# Apex3.net
KiCad netlist of a schematic drawn in EAGLE
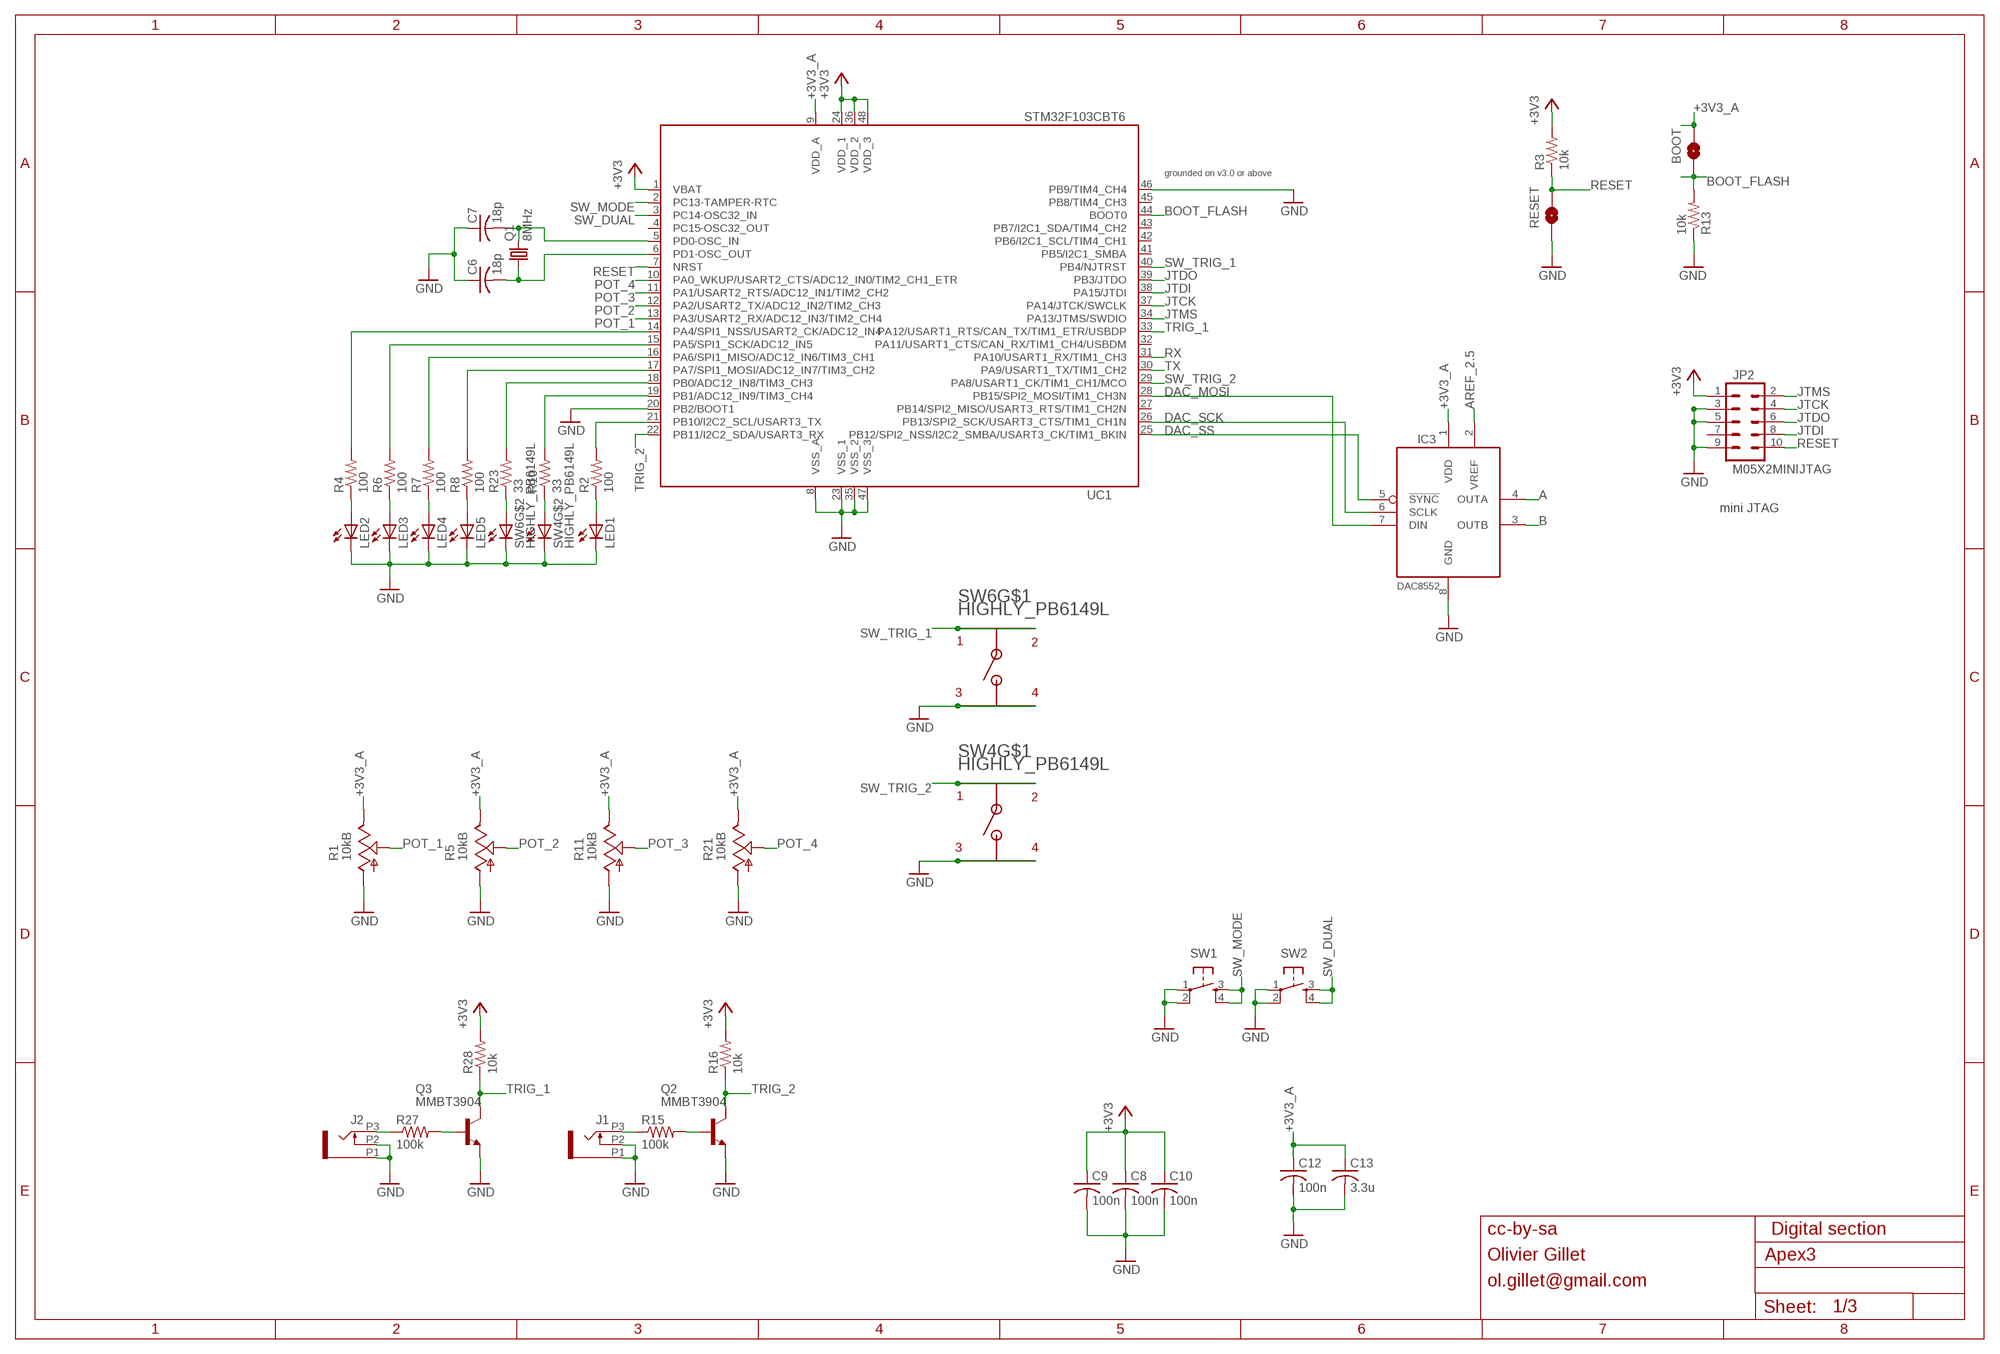
[diagram p0: schematic, sheet 1]
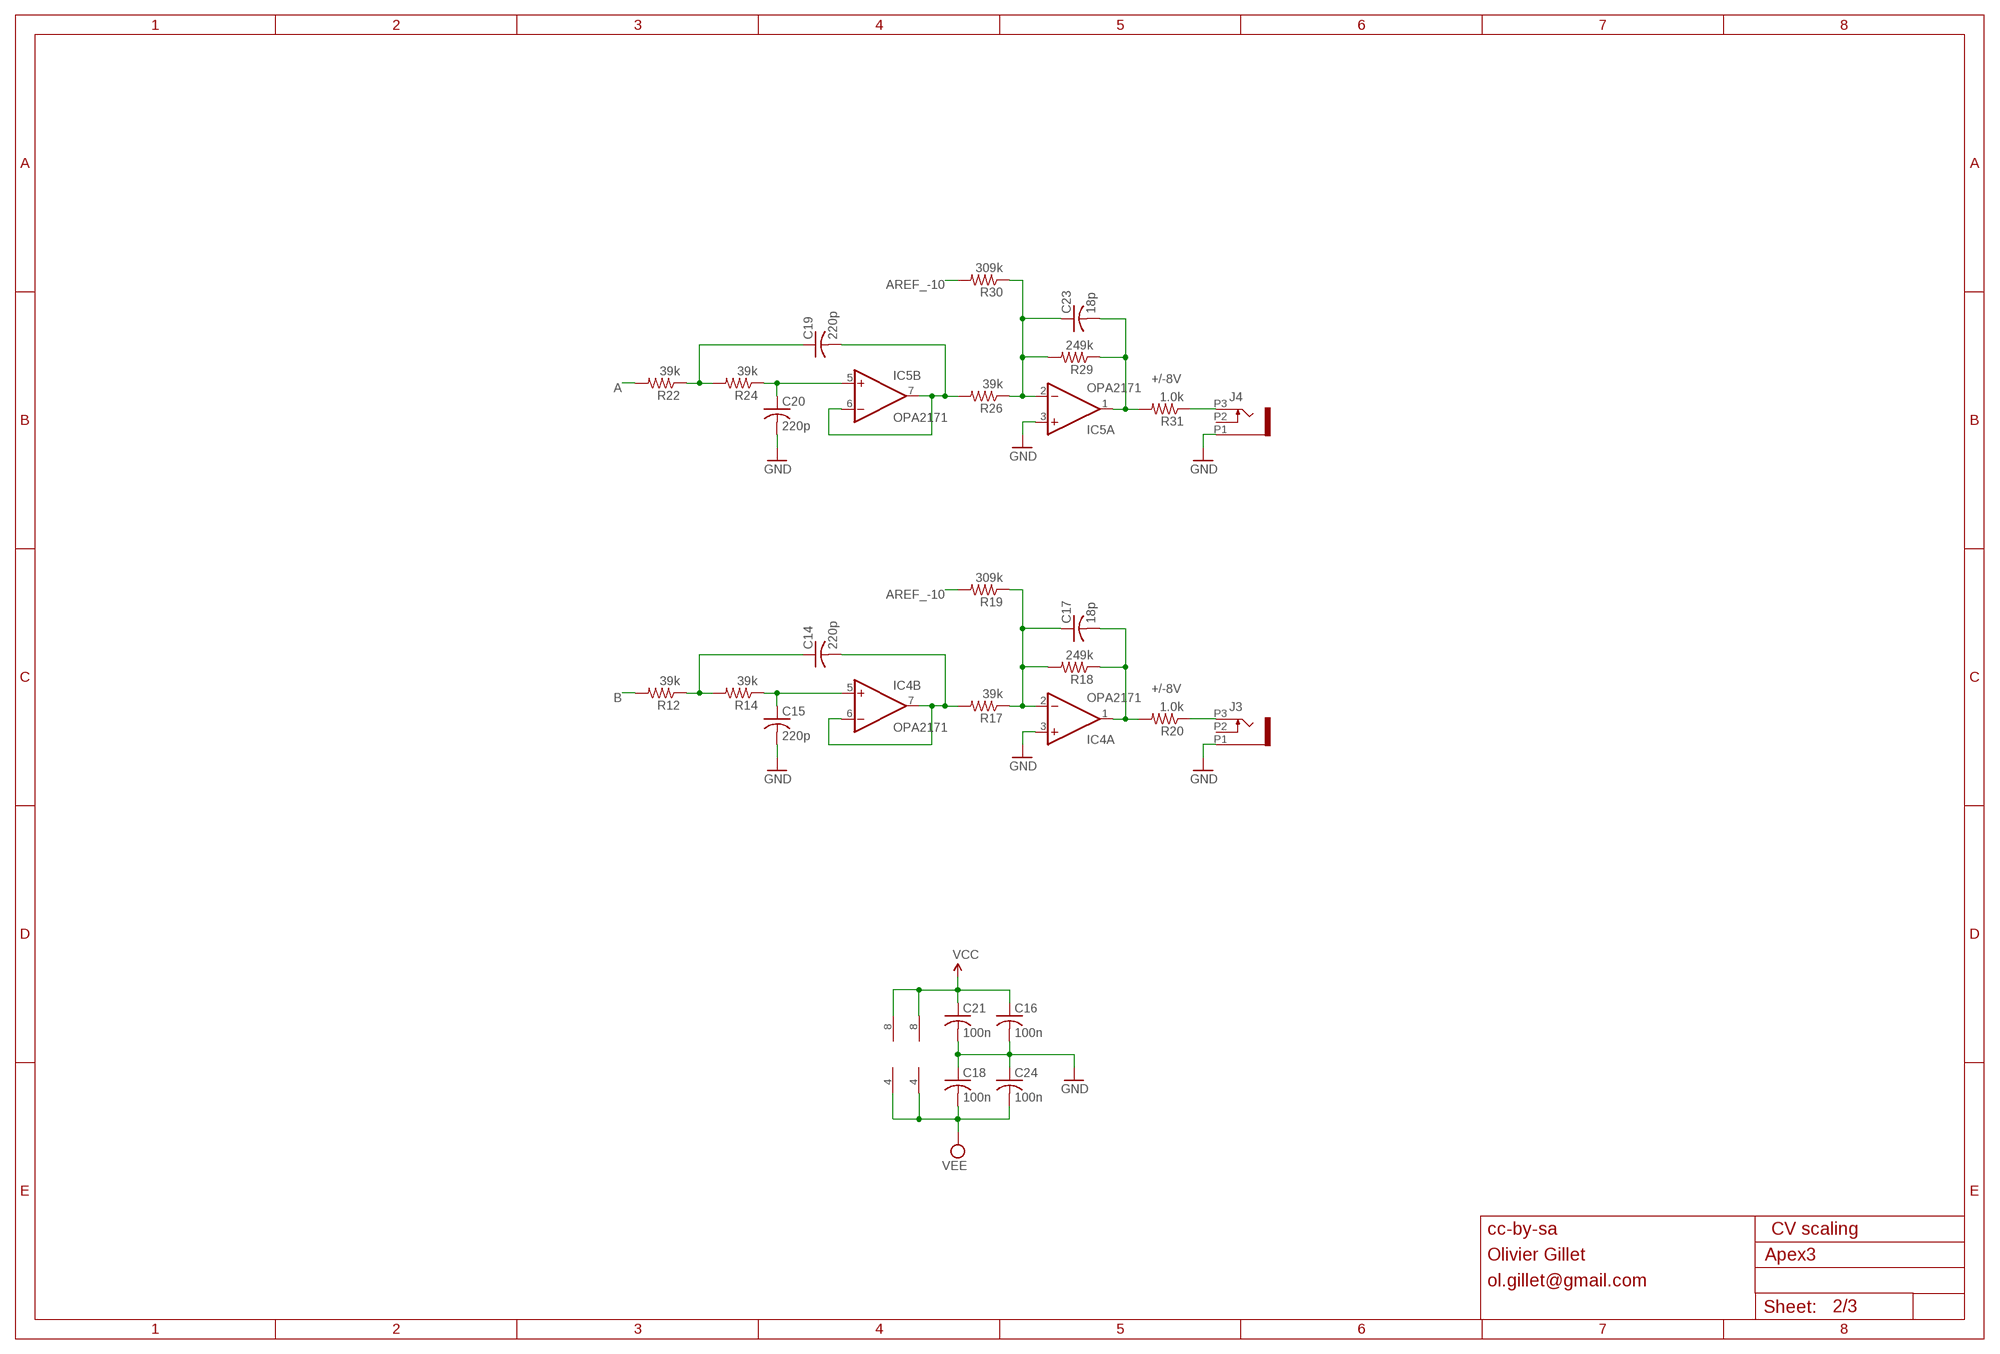
[diagram p1: schematic, sheet 2]
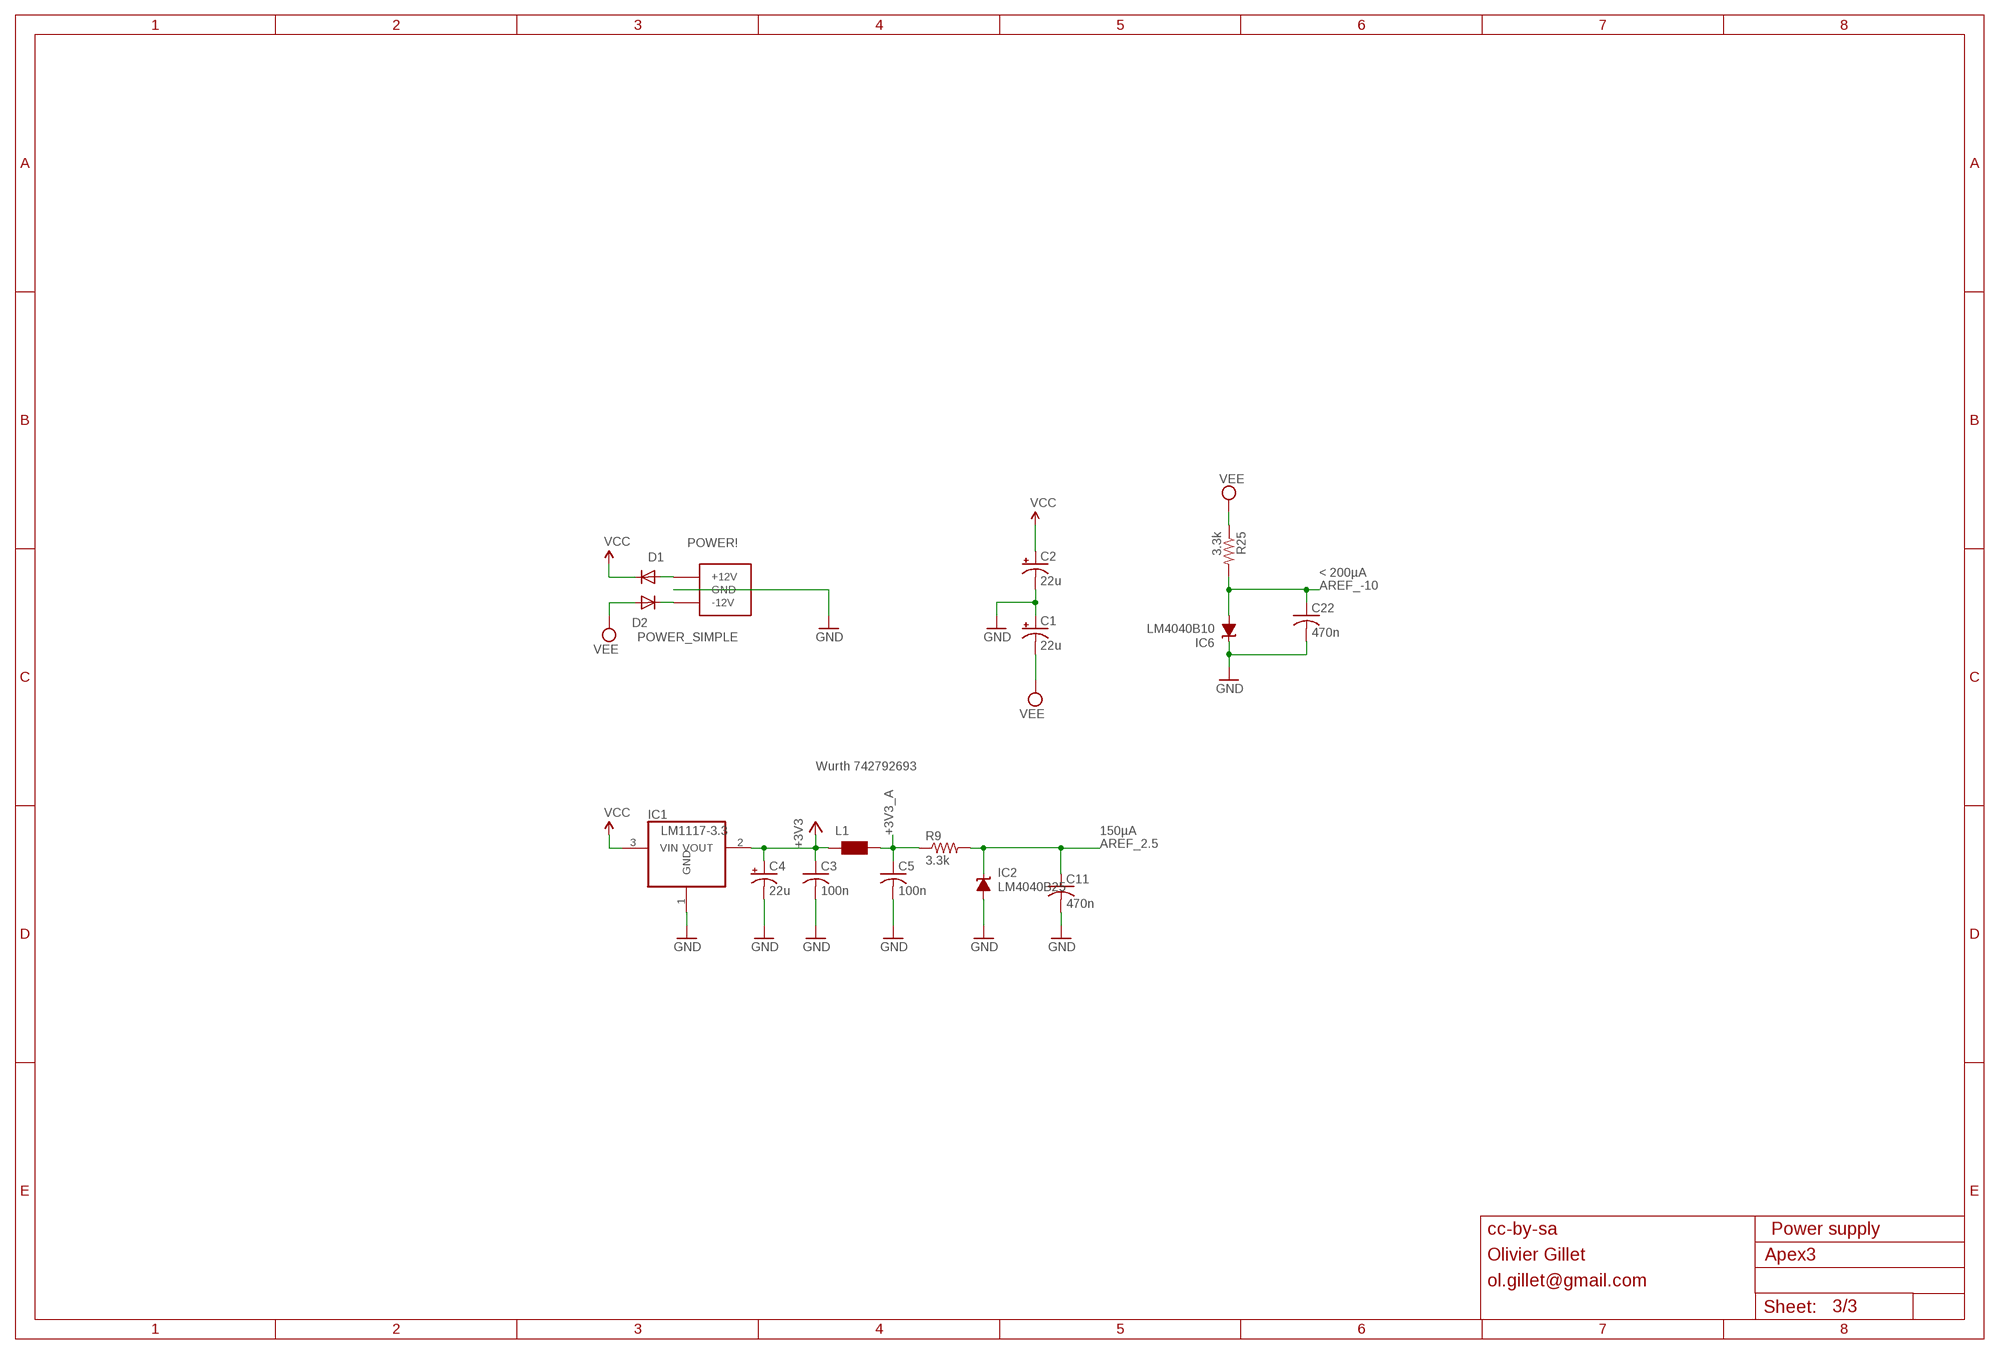
[diagram p2: schematic, sheet 3]

(export (version "E")
  (design (tool "Eeschema 10.0.6"))
  (components
    (comp (ref "C14")
      (value "220p")
      (footprint "eagle-import:C0603")
      (libsource (lib "eagle-import") (part "C-USC0603"))
    )
    (comp (ref "C15")
      (value "220p")
      (footprint "eagle-import:C0603")
      (libsource (lib "eagle-import") (part "C-USC0603"))
    )
    (comp (ref "C16")
      (value "100n")
      (footprint "eagle-import:C0603")
      (libsource (lib "eagle-import") (part "C-USC0603"))
    )
    (comp (ref "C17")
      (value "18p")
      (footprint "eagle-import:C0603")
      (libsource (lib "eagle-import") (part "C-USC0603"))
    )
    (comp (ref "C18")
      (value "100n")
      (footprint "eagle-import:C0603")
      (libsource (lib "eagle-import") (part "C-USC0603"))
    )
    (comp (ref "C19")
      (value "220p")
      (footprint "eagle-import:C0603")
      (libsource (lib "eagle-import") (part "C-USC0603"))
    )
    (comp (ref "C20")
      (value "220p")
      (footprint "eagle-import:C0603")
      (libsource (lib "eagle-import") (part "C-USC0603"))
    )
    (comp (ref "C21")
      (value "100n")
      (footprint "eagle-import:C0603")
      (libsource (lib "eagle-import") (part "C-USC0603"))
    )
    (comp (ref "C23")
      (value "18p")
      (footprint "eagle-import:C0603")
      (libsource (lib "eagle-import") (part "C-USC0603"))
    )
    (comp (ref "C24")
      (value "100n")
      (footprint "eagle-import:C0603")
      (libsource (lib "eagle-import") (part "C-USC0603"))
    )
    (comp (ref "IC4")
      (value "OPA2171")
      (footprint "eagle-import:SO08")
      (libsource (lib "eagle-import") (part "TL072D"))
    )
    (comp (ref "IC5")
      (value "OPA2171")
      (footprint "eagle-import:SO08")
      (libsource (lib "eagle-import") (part "TL072D"))
    )
    (comp (ref "J3")
      (value "OG-PJ301_PJ301_THONKICONN")
      (footprint "eagle-import:OG-PJ301_WQP_PJ_301M6_NO_HOLE")
      (libsource (lib "eagle-import") (part "OG-PJ301_PJ301_THONKICONN"))
    )
    (comp (ref "J4")
      (value "OG-PJ301_PJ301_THONKICONN")
      (footprint "eagle-import:OG-PJ301_WQP_PJ_301M6_NO_HOLE")
      (libsource (lib "eagle-import") (part "OG-PJ301_PJ301_THONKICONN"))
    )
    (comp (ref "R12")
      (value "39k")
      (footprint "eagle-import:R0603")
      (libsource (lib "eagle-import") (part "R-US_R0603"))
    )
    (comp (ref "R14")
      (value "39k")
      (footprint "eagle-import:R0603")
      (libsource (lib "eagle-import") (part "R-US_R0603"))
    )
    (comp (ref "R17")
      (value "39k")
      (footprint "eagle-import:R0603")
      (libsource (lib "eagle-import") (part "R-US_R0603"))
    )
    (comp (ref "R18")
      (value "249k")
      (footprint "eagle-import:R0603")
      (libsource (lib "eagle-import") (part "R-US_R0603"))
    )
    (comp (ref "R19")
      (value "309k")
      (footprint "eagle-import:R0603")
      (libsource (lib "eagle-import") (part "R-US_R0603"))
    )
    (comp (ref "R20")
      (value "1.0k")
      (footprint "eagle-import:R0603")
      (libsource (lib "eagle-import") (part "R-US_R0603"))
    )
    (comp (ref "R22")
      (value "39k")
      (footprint "eagle-import:R0603")
      (libsource (lib "eagle-import") (part "R-US_R0603"))
    )
    (comp (ref "R24")
      (value "39k")
      (footprint "eagle-import:R0603")
      (libsource (lib "eagle-import") (part "R-US_R0603"))
    )
    (comp (ref "R26")
      (value "39k")
      (footprint "eagle-import:R0603")
      (libsource (lib "eagle-import") (part "R-US_R0603"))
    )
    (comp (ref "R29")
      (value "249k")
      (footprint "eagle-import:R0603")
      (libsource (lib "eagle-import") (part "R-US_R0603"))
    )
    (comp (ref "R30")
      (value "309k")
      (footprint "eagle-import:R0603")
      (libsource (lib "eagle-import") (part "R-US_R0603"))
    )
    (comp (ref "R31")
      (value "1.0k")
      (footprint "eagle-import:R0603")
      (libsource (lib "eagle-import") (part "R-US_R0603"))
    )
    (comp (ref "C1")
      (value "22u")
      (footprint "eagle-import:PANASONIC_C")
      (libsource (lib "eagle-import") (part "CPOL-USC"))
    )
    (comp (ref "C2")
      (value "22u")
      (footprint "eagle-import:PANASONIC_C")
      (libsource (lib "eagle-import") (part "CPOL-USC"))
    )
    (comp (ref "C3")
      (value "100n")
      (footprint "eagle-import:C0603")
      (libsource (lib "eagle-import") (part "C-USC0603"))
    )
    (comp (ref "C4")
      (value "22u")
      (footprint "eagle-import:PANASONIC_C")
      (libsource (lib "eagle-import") (part "CPOL-USC"))
    )
    (comp (ref "C5")
      (value "100n")
      (footprint "eagle-import:C0603")
      (libsource (lib "eagle-import") (part "C-USC0603"))
    )
    (comp (ref "C11")
      (value "470n")
      (footprint "eagle-import:C0603")
      (libsource (lib "eagle-import") (part "C-USC0603"))
    )
    (comp (ref "C22")
      (value "470n")
      (footprint "eagle-import:C0603")
      (libsource (lib "eagle-import") (part "C-USC0603"))
    )
    (comp (ref "D1")
      (value "1N5819HW")
      (footprint "eagle-import:SOD123")
      (libsource (lib "eagle-import") (part "DIODE-SOD123"))
    )
    (comp (ref "D2")
      (value "1N5819HW")
      (footprint "eagle-import:SOD123")
      (libsource (lib "eagle-import") (part "DIODE-SOD123"))
    )
    (comp (ref "IC1")
      (value "LM1117-3.3")
      (footprint "eagle-import:SOT223")
      (libsource (lib "eagle-import") (part "REG1117"))
    )
    (comp (ref "IC2")
      (value "LM4040B25")
      (footprint "eagle-import:DBZ_R-PDSO-G3")
      (libsource (lib "eagle-import") (part "LM4041DBZB12"))
    )
    (comp (ref "IC6")
      (value "LM4040B10")
      (footprint "eagle-import:DBZ_R-PDSO-G3")
      (libsource (lib "eagle-import") (part "LM4041DBZB12"))
    )
    (comp (ref "L1")
      (value "WE-CBF_0603")
      (footprint "eagle-import:0603")
      (libsource (lib "eagle-import") (part "WE-CBF_0603"))
    )
    (comp (ref "POWER!")
      (value "POWER_SIMPLE")
      (footprint "eagle-import:2X05_SMT_HEADER")
      (libsource (lib "eagle-import") (part "POWER_SIMPLE"))
    )
    (comp (ref "R9")
      (value "3.3k")
      (footprint "eagle-import:R0603")
      (libsource (lib "eagle-import") (part "R-US_R0603"))
    )
    (comp (ref "R25")
      (value "3.3k")
      (footprint "eagle-import:R0603")
      (libsource (lib "eagle-import") (part "R-US_R0603"))
    )
    (comp (ref "BOOT")
      (value "BOOT")
      (footprint "eagle-import:SMT-JUMPER_2_NO_SILK")
      (libsource (lib "eagle-import") (part "JUMPER-SMT_2_NO_SILK"))
    )
    (comp (ref "C6")
      (value "18p")
      (footprint "eagle-import:C0603")
      (libsource (lib "eagle-import") (part "C-USC0603"))
    )
    (comp (ref "C7")
      (value "18p")
      (footprint "eagle-import:C0603")
      (libsource (lib "eagle-import") (part "C-USC0603"))
    )
    (comp (ref "C8")
      (value "100n")
      (footprint "eagle-import:C0603")
      (libsource (lib "eagle-import") (part "C-USC0603"))
    )
    (comp (ref "C9")
      (value "100n")
      (footprint "eagle-import:C0603")
      (libsource (lib "eagle-import") (part "C-USC0603"))
    )
    (comp (ref "C10")
      (value "100n")
      (footprint "eagle-import:C0603")
      (libsource (lib "eagle-import") (part "C-USC0603"))
    )
    (comp (ref "C12")
      (value "100n")
      (footprint "eagle-import:C0603")
      (libsource (lib "eagle-import") (part "C-USC0603"))
    )
    (comp (ref "C13")
      (value "3.3u")
      (footprint "eagle-import:C0603")
      (libsource (lib "eagle-import") (part "C-USC0603"))
    )
    (comp (ref "IC3")
      (value "DAC8552")
      (footprint "eagle-import:MSOP-8")
      (libsource (lib "eagle-import") (part "DAC8552"))
    )
    (comp (ref "J1")
      (value "OG-PJ301_PJ301_THONKICONN")
      (footprint "eagle-import:OG-PJ301_WQP_PJ_301M6_NO_HOLE")
      (libsource (lib "eagle-import") (part "OG-PJ301_PJ301_THONKICONN"))
    )
    (comp (ref "J2")
      (value "OG-PJ301_PJ301_THONKICONN")
      (footprint "eagle-import:OG-PJ301_WQP_PJ_301M6_NO_HOLE")
      (libsource (lib "eagle-import") (part "OG-PJ301_PJ301_THONKICONN"))
    )
    (comp (ref "JP2")
      (value "M05X2MINIJTAG")
      (footprint "eagle-import:2X5-1.27")
      (libsource (lib "eagle-import") (part "M05X2MINIJTAG"))
    )
    (comp (ref "LED1")
      (value "LED3MM")
      (footprint "eagle-import:LED3MM")
      (libsource (lib "eagle-import") (part "LED3MM"))
    )
    (comp (ref "LED2")
      (value "LED3MM")
      (footprint "eagle-import:LED3MM")
      (libsource (lib "eagle-import") (part "LED3MM"))
    )
    (comp (ref "LED3")
      (value "LED3MM")
      (footprint "eagle-import:LED3MM")
      (libsource (lib "eagle-import") (part "LED3MM"))
    )
    (comp (ref "LED4")
      (value "LED3MM")
      (footprint "eagle-import:LED3MM")
      (libsource (lib "eagle-import") (part "LED3MM"))
    )
    (comp (ref "LED5")
      (value "LED3MM")
      (footprint "eagle-import:LED3MM")
      (libsource (lib "eagle-import") (part "LED3MM"))
    )
    (comp (ref "Q1")
      (value "8MHz")
      (footprint "eagle-import:HC49UP")
      (libsource (lib "eagle-import") (part "CRYSTALHC49UP"))
    )
    (comp (ref "Q2")
      (value "MMBT3904")
      (footprint "eagle-import:SOT23-BEC")
      (libsource (lib "eagle-import") (part "-NPN-SOT23-BECMMBT3904LT1"))
    )
    (comp (ref "Q3")
      (value "MMBT3904")
      (footprint "eagle-import:SOT23-BEC")
      (libsource (lib "eagle-import") (part "-NPN-SOT23-BECMMBT3904LT1"))
    )
    (comp (ref "R1")
      (value "10kB")
      (footprint "eagle-import:POT-ALPS_ALPS_POT_VERTICAL")
      (libsource (lib "eagle-import") (part "POT-ALPS_POT_USVERTICAL"))
    )
    (comp (ref "R2")
      (value "100")
      (footprint "eagle-import:R0603")
      (libsource (lib "eagle-import") (part "R-US_R0603"))
    )
    (comp (ref "R3")
      (value "10k")
      (footprint "eagle-import:R0603")
      (libsource (lib "eagle-import") (part "R-US_R0603"))
    )
    (comp (ref "R4")
      (value "100")
      (footprint "eagle-import:R0603")
      (libsource (lib "eagle-import") (part "R-US_R0603"))
    )
    (comp (ref "R5")
      (value "10kB")
      (footprint "eagle-import:POT-ALPS_ALPS_POT_VERTICAL")
      (libsource (lib "eagle-import") (part "POT-ALPS_POT_USVERTICAL"))
    )
    (comp (ref "R6")
      (value "100")
      (footprint "eagle-import:R0603")
      (libsource (lib "eagle-import") (part "R-US_R0603"))
    )
    (comp (ref "R7")
      (value "100")
      (footprint "eagle-import:R0603")
      (libsource (lib "eagle-import") (part "R-US_R0603"))
    )
    (comp (ref "R8")
      (value "100")
      (footprint "eagle-import:R0603")
      (libsource (lib "eagle-import") (part "R-US_R0603"))
    )
    (comp (ref "R10")
      (value "33")
      (footprint "eagle-import:R0603")
      (libsource (lib "eagle-import") (part "R-US_R0603"))
    )
    (comp (ref "R11")
      (value "10kB")
      (footprint "eagle-import:POT-ALPS_ALPS_POT_VERTICAL")
      (libsource (lib "eagle-import") (part "POT-ALPS_POT_USVERTICAL"))
    )
    (comp (ref "R13")
      (value "10k")
      (footprint "eagle-import:R0603")
      (libsource (lib "eagle-import") (part "R-US_R0603"))
    )
    (comp (ref "R15")
      (value "100k")
      (footprint "eagle-import:R0603")
      (libsource (lib "eagle-import") (part "R-US_R0603"))
    )
    (comp (ref "R16")
      (value "10k")
      (footprint "eagle-import:R0603")
      (libsource (lib "eagle-import") (part "R-US_R0603"))
    )
    (comp (ref "R21")
      (value "10kB")
      (footprint "eagle-import:POT-ALPS_ALPS_POT_VERTICAL")
      (libsource (lib "eagle-import") (part "POT-ALPS_POT_USVERTICAL"))
    )
    (comp (ref "R23")
      (value "33")
      (footprint "eagle-import:R0603")
      (libsource (lib "eagle-import") (part "R-US_R0603"))
    )
    (comp (ref "R27")
      (value "100k")
      (footprint "eagle-import:R0603")
      (libsource (lib "eagle-import") (part "R-US_R0603"))
    )
    (comp (ref "R28")
      (value "10k")
      (footprint "eagle-import:R0603")
      (libsource (lib "eagle-import") (part "R-US_R0603"))
    )
    (comp (ref "RESET")
      (value "RESET")
      (footprint "eagle-import:SMT-JUMPER_2_NO_SILK")
      (libsource (lib "eagle-import") (part "JUMPER-SMT_2_NO_SILK"))
    )
    (comp (ref "SW1")
      (value "TAC_SWITCHPTH")
      (footprint "eagle-import:TACTILE-PTH")
      (libsource (lib "eagle-import") (part "TAC_SWITCHPTH"))
    )
    (comp (ref "SW2")
      (value "TAC_SWITCHPTH")
      (footprint "eagle-import:TACTILE-PTH")
      (libsource (lib "eagle-import") (part "TAC_SWITCHPTH"))
    )
    (comp (ref "SW4")
      (value "HIGHLY_PB6149L")
      (footprint "eagle-import:HIGHLY_PB64149L")
      (libsource (lib "eagle-import") (part "HIGHLY_PB6149L"))
    )
    (comp (ref "SW6")
      (value "HIGHLY_PB6149L")
      (footprint "eagle-import:HIGHLY_PB64149L")
      (libsource (lib "eagle-import") (part "HIGHLY_PB6149L"))
    )
    (comp (ref "UC1")
      (value "STM32F103CBT6")
      (footprint "eagle-import:LQFP48")
      (libsource (lib "eagle-import") (part "STM32F103CB"))
    )
  )
  (nets
    (net (code "1") (name "+3V3") (class "Default")
      (node (ref "C10") (pin "1") (pinfunction "1_1") (pintype "passive"))
      (node (ref "C3") (pin "1") (pinfunction "1_1") (pintype "passive"))
      (node (ref "C4") (pin "+") (pinfunction "+_+") (pintype "passive"))
      (node (ref "C8") (pin "1") (pinfunction "1_1") (pintype "passive"))
      (node (ref "C9") (pin "1") (pinfunction "1_1") (pintype "passive"))
      (node (ref "IC1") (pin "2") (pinfunction "VOUT_2") (pintype "output"))
      (node (ref "JP2") (pin "1") (pinfunction "1_1") (pintype "passive"))
      (node (ref "L1") (pin "1") (pinfunction "1_1") (pintype "passive"))
      (node (ref "R16") (pin "2") (pinfunction "2_2") (pintype "passive"))
      (node (ref "R28") (pin "2") (pinfunction "2_2") (pintype "passive"))
      (node (ref "R3") (pin "2") (pinfunction "2_2") (pintype "passive"))
      (node (ref "UC1") (pin "1") (pinfunction "VBAT_1") (pintype "power_in"))
      (node (ref "UC1") (pin "24") (pinfunction "VDD_1_24") (pintype "power_in"))
      (node (ref "UC1") (pin "36") (pinfunction "VDD_2_36") (pintype "power_in"))
      (node (ref "UC1") (pin "48") (pinfunction "VDD_3_48") (pintype "power_in"))
    )
    (net (code "2") (name "+3V3_A") (class "Default")
      (node (ref "BOOT") (pin "2") (pinfunction "2_2") (pintype "passive"))
      (node (ref "C12") (pin "1") (pinfunction "1_1") (pintype "passive"))
      (node (ref "C13") (pin "1") (pinfunction "1_1") (pintype "passive"))
      (node (ref "C5") (pin "1") (pinfunction "1_1") (pintype "passive"))
      (node (ref "IC3") (pin "1") (pinfunction "VDD_1") (pintype "power_in"))
      (node (ref "L1") (pin "2") (pinfunction "2_2") (pintype "passive"))
      (node (ref "R1") (pin "P$1") (pinfunction "E_P$1") (pintype "passive"))
      (node (ref "R11") (pin "P$1") (pinfunction "E_P$1") (pintype "passive"))
      (node (ref "R21") (pin "P$1") (pinfunction "E_P$1") (pintype "passive"))
      (node (ref "R5") (pin "P$1") (pinfunction "E_P$1") (pintype "passive"))
      (node (ref "R9") (pin "1") (pinfunction "1_1") (pintype "passive"))
      (node (ref "UC1") (pin "9") (pinfunction "VDD_A_9") (pintype "power_in"))
    )
    (net (code "3") (name "A") (class "Default")
      (node (ref "IC3") (pin "4") (pinfunction "OUTA_4") (pintype "output"))
      (node (ref "R22") (pin "2") (pinfunction "2_2") (pintype "passive"))
    )
    (net (code "4") (name "AREF_-10") (class "Default")
      (node (ref "C22") (pin "1") (pinfunction "1_1") (pintype "passive"))
      (node (ref "IC6") (pin "2") (pinfunction "A_2") (pintype "passive"))
      (node (ref "R19") (pin "2") (pinfunction "2_2") (pintype "passive"))
      (node (ref "R25") (pin "2") (pinfunction "2_2") (pintype "passive"))
      (node (ref "R30") (pin "2") (pinfunction "2_2") (pintype "passive"))
    )
    (net (code "5") (name "AREF_2.5") (class "Default")
      (node (ref "C11") (pin "1") (pinfunction "1_1") (pintype "passive"))
      (node (ref "IC2") (pin "1") (pinfunction "C_1") (pintype "passive"))
      (node (ref "IC3") (pin "2") (pinfunction "VREF_2") (pintype "power_in"))
      (node (ref "R9") (pin "2") (pinfunction "2_2") (pintype "passive"))
    )
    (net (code "6") (name "B") (class "Default")
      (node (ref "IC3") (pin "3") (pinfunction "OUTB_3") (pintype "input"))
      (node (ref "R12") (pin "2") (pinfunction "2_2") (pintype "passive"))
    )
    (net (code "7") (name "BOOT_FLASH") (class "Default")
      (node (ref "BOOT") (pin "1") (pinfunction "1_1") (pintype "passive"))
      (node (ref "R13") (pin "2") (pinfunction "2_2") (pintype "passive"))
      (node (ref "UC1") (pin "44") (pinfunction "BOOT0_44") (pintype "input"))
    )
    (net (code "8") (name "DAC_MOSI") (class "Default")
      (node (ref "IC3") (pin "7") (pinfunction "DIN_7") (pintype "bidirectional"))
      (node (ref "UC1") (pin "28") (pinfunction "PB15/SPI2_MOSI/TIM1_CH3N_28") (pintype "input"))
    )
    (net (code "9") (name "DAC_SCK") (class "Default")
      (node (ref "IC3") (pin "6") (pinfunction "SCLK_6") (pintype "bidirectional"))
      (node (ref "UC1") (pin "26") (pinfunction "PB13/SPI2_SCK/USART3_CTS/TIM1_CH1N_26") (pintype "input"))
    )
    (net (code "10") (name "DAC_SS") (class "Default")
      (node (ref "IC3") (pin "5") (pinfunction "~{SYNC}_5") (pintype "bidirectional"))
      (node (ref "UC1") (pin "25") (pinfunction "PB12/SPI2_NSS/I2C2_SMBA/USART3_CK/TIM1_BKIN_25") (pintype "input"))
    )
    (net (code "11") (name "GND") (class "Default")
      (node (ref "C1") (pin "+") (pinfunction "+_+") (pintype "passive"))
      (node (ref "C10") (pin "2") (pinfunction "2_2") (pintype "passive"))
      (node (ref "C11") (pin "2") (pinfunction "2_2") (pintype "passive"))
      (node (ref "C12") (pin "2") (pinfunction "2_2") (pintype "passive"))
      (node (ref "C13") (pin "2") (pinfunction "2_2") (pintype "passive"))
      (node (ref "C15") (pin "2") (pinfunction "2_2") (pintype "passive"))
      (node (ref "C16") (pin "2") (pinfunction "2_2") (pintype "passive"))
      (node (ref "C18") (pin "1") (pinfunction "1_1") (pintype "passive"))
      (node (ref "C2") (pin "-") (pinfunction "-_-") (pintype "passive"))
      (node (ref "C20") (pin "2") (pinfunction "2_2") (pintype "passive"))
      (node (ref "C21") (pin "2") (pinfunction "2_2") (pintype "passive"))
      (node (ref "C22") (pin "2") (pinfunction "2_2") (pintype "passive"))
      (node (ref "C24") (pin "1") (pinfunction "1_1") (pintype "passive"))
      (node (ref "C3") (pin "2") (pinfunction "2_2") (pintype "passive"))
      (node (ref "C4") (pin "-") (pinfunction "-_-") (pintype "passive"))
      (node (ref "C5") (pin "2") (pinfunction "2_2") (pintype "passive"))
      (node (ref "C6") (pin "1") (pinfunction "1_1") (pintype "passive"))
      (node (ref "C7") (pin "1") (pinfunction "1_1") (pintype "passive"))
      (node (ref "C8") (pin "2") (pinfunction "2_2") (pintype "passive"))
      (node (ref "C9") (pin "2") (pinfunction "2_2") (pintype "passive"))
      (node (ref "IC1") (pin "1") (pinfunction "GND_1") (pintype "power_in"))
      (node (ref "IC2") (pin "2") (pinfunction "A_2") (pintype "passive"))
      (node (ref "IC3") (pin "8") (pinfunction "GND_8") (pintype "power_in"))
      (node (ref "IC4") (pin "3") (pinfunction "+IN_3") (pintype "input"))
      (node (ref "IC5") (pin "3") (pinfunction "+IN_3") (pintype "input"))
      (node (ref "IC6") (pin "1") (pinfunction "C_1") (pintype "passive"))
      (node (ref "J1") (pin "P1") (pinfunction "1_P1") (pintype "passive"))
      (node (ref "J1") (pin "P2") (pinfunction "2_P2") (pintype "passive"))
      (node (ref "J2") (pin "P1") (pinfunction "1_P1") (pintype "passive"))
      (node (ref "J2") (pin "P2") (pinfunction "2_P2") (pintype "passive"))
      (node (ref "J3") (pin "P1") (pinfunction "1_P1") (pintype "passive"))
      (node (ref "J4") (pin "P1") (pinfunction "1_P1") (pintype "passive"))
      (node (ref "JP2") (pin "3") (pinfunction "3_3") (pintype "passive"))
      (node (ref "JP2") (pin "5") (pinfunction "5_5") (pintype "passive"))
      (node (ref "JP2") (pin "9") (pinfunction "9_9") (pintype "passive"))
      (node (ref "LED1") (pin "K") (pinfunction "C_K") (pintype "passive"))
      (node (ref "LED2") (pin "K") (pinfunction "C_K") (pintype "passive"))
      (node (ref "LED3") (pin "K") (pinfunction "C_K") (pintype "passive"))
      (node (ref "LED4") (pin "K") (pinfunction "C_K") (pintype "passive"))
      (node (ref "LED5") (pin "K") (pinfunction "C_K") (pintype "passive"))
      (node (ref "POWER!") (pin "3") (pinfunction "GND_3") (pintype "bidirectional"))
      (node (ref "POWER!") (pin "4") (pinfunction "GND_4") (pintype "bidirectional"))
      (node (ref "POWER!") (pin "5") (pinfunction "GND_5") (pintype "bidirectional"))
      (node (ref "POWER!") (pin "6") (pinfunction "GND_6") (pintype "bidirectional"))
      (node (ref "POWER!") (pin "7") (pinfunction "GND_7") (pintype "bidirectional"))
      (node (ref "POWER!") (pin "8") (pinfunction "GND_8") (pintype "bidirectional"))
      (node (ref "Q2") (pin "E") (pinfunction "E_E") (pintype "passive"))
      (node (ref "Q3") (pin "E") (pinfunction "E_E") (pintype "passive"))
      (node (ref "R1") (pin "P$3") (pinfunction "A_P$3") (pintype "passive"))
      (node (ref "R11") (pin "P$3") (pinfunction "A_P$3") (pintype "passive"))
      (node (ref "R13") (pin "1") (pinfunction "1_1") (pintype "passive"))
      (node (ref "R21") (pin "P$3") (pinfunction "A_P$3") (pintype "passive"))
      (node (ref "R5") (pin "P$3") (pinfunction "A_P$3") (pintype "passive"))
      (node (ref "RESET") (pin "1") (pinfunction "1_1") (pintype "passive"))
      (node (ref "SW1") (pin "1") (pinfunction "1_1") (pintype "passive"))
      (node (ref "SW1") (pin "2") (pinfunction "2_2") (pintype "passive"))
      (node (ref "SW2") (pin "1") (pinfunction "1_1") (pintype "passive"))
      (node (ref "SW2") (pin "2") (pinfunction "2_2") (pintype "passive"))
      (node (ref "SW4") (pin "L2") (pinfunction "L2_L2") (pintype "passive"))
      (node (ref "SW4") (pin "P$3") (pinfunction "P$3_P$3") (pintype "bidirectional"))
      (node (ref "SW4") (pin "P$4") (pinfunction "P$4_P$4") (pintype "bidirectional"))
      (node (ref "SW6") (pin "L2") (pinfunction "L2_L2") (pintype "passive"))
      (node (ref "SW6") (pin "P$3") (pinfunction "P$3_P$3") (pintype "bidirectional"))
      (node (ref "SW6") (pin "P$4") (pinfunction "P$4_P$4") (pintype "bidirectional"))
      (node (ref "UC1") (pin "20") (pinfunction "PB2/BOOT1_20") (pintype "bidirectional"))
      (node (ref "UC1") (pin "23") (pinfunction "VSS_1_23") (pintype "power_in"))
      (node (ref "UC1") (pin "35") (pinfunction "VSS_2_35") (pintype "power_in"))
      (node (ref "UC1") (pin "46") (pinfunction "PB9/TIM4_CH4_46") (pintype "input"))
      (node (ref "UC1") (pin "47") (pinfunction "VSS_3_47") (pintype "power_in"))
      (node (ref "UC1") (pin "8") (pinfunction "VSS_A_8") (pintype "power_in"))
    )
    (net (code "12") (name "JTCK") (class "Default")
      (node (ref "JP2") (pin "4") (pinfunction "4_4") (pintype "passive"))
      (node (ref "UC1") (pin "37") (pinfunction "PA14/JTCK/SWCLK_37") (pintype "bidirectional"))
    )
    (net (code "13") (name "JTDI") (class "Default")
      (node (ref "JP2") (pin "8") (pinfunction "8_8") (pintype "passive"))
      (node (ref "UC1") (pin "38") (pinfunction "PA15/JTDI_38") (pintype "bidirectional"))
    )
    (net (code "14") (name "JTDO") (class "Default")
      (node (ref "JP2") (pin "6") (pinfunction "6_6") (pintype "passive"))
      (node (ref "UC1") (pin "39") (pinfunction "PB3/JTDO_39") (pintype "bidirectional"))
    )
    (net (code "15") (name "JTMS") (class "Default")
      (node (ref "JP2") (pin "2") (pinfunction "2_2") (pintype "passive"))
      (node (ref "UC1") (pin "34") (pinfunction "PA13/JTMS/SWDIO_34") (pintype "bidirectional"))
    )
    (net (code "16") (name "Net-(C14-Pad1)") (class "Default")
      (node (ref "C14") (pin "1") (pinfunction "1_1") (pintype "passive"))
      (node (ref "R12") (pin "1") (pinfunction "1_1") (pintype "passive"))
      (node (ref "R14") (pin "2") (pinfunction "2_2") (pintype "passive"))
    )
    (net (code "17") (name "Net-(C19-Pad1)") (class "Default")
      (node (ref "C19") (pin "1") (pinfunction "1_1") (pintype "passive"))
      (node (ref "R22") (pin "1") (pinfunction "1_1") (pintype "passive"))
      (node (ref "R24") (pin "2") (pinfunction "2_2") (pintype "passive"))
    )
    (net (code "18") (name "Net-(D1-PadA)") (class "Default")
      (node (ref "D1") (pin "A") (pinfunction "A_A") (pintype "passive"))
      (node (ref "POWER!") (pin "10") (pinfunction "+12V_10") (pintype "bidirectional"))
      (node (ref "POWER!") (pin "9") (pinfunction "+12V_9") (pintype "bidirectional"))
    )
    (net (code "19") (name "Net-(D2-PadC)") (class "Default")
      (node (ref "D2") (pin "C") (pinfunction "C_C") (pintype "passive"))
      (node (ref "POWER!") (pin "1") (pinfunction "-12V_1") (pintype "bidirectional"))
      (node (ref "POWER!") (pin "2") (pinfunction "-12V_2") (pintype "bidirectional"))
    )
    (net (code "20") (name "Net-(IC4A--IN)") (class "Default")
      (node (ref "C17") (pin "1") (pinfunction "1_1") (pintype "passive"))
      (node (ref "IC4") (pin "2") (pinfunction "-IN_2") (pintype "input"))
      (node (ref "R17") (pin "1") (pinfunction "1_1") (pintype "passive"))
      (node (ref "R18") (pin "2") (pinfunction "2_2") (pintype "passive"))
      (node (ref "R19") (pin "1") (pinfunction "1_1") (pintype "passive"))
    )
    (net (code "21") (name "Net-(IC4A-OUT)") (class "Default")
      (node (ref "C17") (pin "2") (pinfunction "2_2") (pintype "passive"))
      (node (ref "IC4") (pin "1") (pinfunction "OUT_1") (pintype "output"))
      (node (ref "R18") (pin "1") (pinfunction "1_1") (pintype "passive"))
      (node (ref "R20") (pin "2") (pinfunction "2_2") (pintype "passive"))
    )
    (net (code "22") (name "Net-(IC4B-+IN)") (class "Default")
      (node (ref "C15") (pin "1") (pinfunction "1_1") (pintype "passive"))
      (node (ref "IC4") (pin "5") (pinfunction "+IN_5") (pintype "input"))
      (node (ref "R14") (pin "1") (pinfunction "1_1") (pintype "passive"))
    )
    (net (code "23") (name "Net-(IC4B--IN)") (class "Default")
      (node (ref "C14") (pin "2") (pinfunction "2_2") (pintype "passive"))
      (node (ref "IC4") (pin "6") (pinfunction "-IN_6") (pintype "input"))
      (node (ref "IC4") (pin "7") (pinfunction "OUT_7") (pintype "output"))
      (node (ref "R17") (pin "2") (pinfunction "2_2") (pintype "passive"))
    )
    (net (code "24") (name "Net-(IC5A--IN)") (class "Default")
      (node (ref "C23") (pin "1") (pinfunction "1_1") (pintype "passive"))
      (node (ref "IC5") (pin "2") (pinfunction "-IN_2") (pintype "input"))
      (node (ref "R26") (pin "1") (pinfunction "1_1") (pintype "passive"))
      (node (ref "R29") (pin "2") (pinfunction "2_2") (pintype "passive"))
      (node (ref "R30") (pin "1") (pinfunction "1_1") (pintype "passive"))
    )
    (net (code "25") (name "Net-(IC5A-OUT)") (class "Default")
      (node (ref "C23") (pin "2") (pinfunction "2_2") (pintype "passive"))
      (node (ref "IC5") (pin "1") (pinfunction "OUT_1") (pintype "output"))
      (node (ref "R29") (pin "1") (pinfunction "1_1") (pintype "passive"))
      (node (ref "R31") (pin "2") (pinfunction "2_2") (pintype "passive"))
    )
    (net (code "26") (name "Net-(IC5B-+IN)") (class "Default")
      (node (ref "C20") (pin "1") (pinfunction "1_1") (pintype "passive"))
      (node (ref "IC5") (pin "5") (pinfunction "+IN_5") (pintype "input"))
      (node (ref "R24") (pin "1") (pinfunction "1_1") (pintype "passive"))
    )
    (net (code "27") (name "Net-(IC5B--IN)") (class "Default")
      (node (ref "C19") (pin "2") (pinfunction "2_2") (pintype "passive"))
      (node (ref "IC5") (pin "6") (pinfunction "-IN_6") (pintype "input"))
      (node (ref "IC5") (pin "7") (pinfunction "OUT_7") (pintype "output"))
      (node (ref "R26") (pin "2") (pinfunction "2_2") (pintype "passive"))
    )
    (net (code "28") (name "Net-(J1-3)") (class "Default")
      (node (ref "J1") (pin "P3") (pinfunction "3_P3") (pintype "passive"))
      (node (ref "R15") (pin "1") (pinfunction "1_1") (pintype "passive"))
    )
    (net (code "29") (name "Net-(J2-3)") (class "Default")
      (node (ref "J2") (pin "P3") (pinfunction "3_P3") (pintype "passive"))
      (node (ref "R27") (pin "1") (pinfunction "1_1") (pintype "passive"))
    )
    (net (code "30") (name "Net-(J3-3)") (class "Default")
      (node (ref "J3") (pin "P3") (pinfunction "3_P3") (pintype "passive"))
      (node (ref "R20") (pin "1") (pinfunction "1_1") (pintype "passive"))
    )
    (net (code "31") (name "Net-(J4-3)") (class "Default")
      (node (ref "J4") (pin "P3") (pinfunction "3_P3") (pintype "passive"))
      (node (ref "R31") (pin "1") (pinfunction "1_1") (pintype "passive"))
    )
    (net (code "32") (name "Net-(LED1-PadA)") (class "Default")
      (node (ref "LED1") (pin "A") (pinfunction "A_A") (pintype "passive"))
      (node (ref "R2") (pin "1") (pinfunction "1_1") (pintype "passive"))
    )
    (net (code "33") (name "Net-(LED2-PadA)") (class "Default")
      (node (ref "LED2") (pin "A") (pinfunction "A_A") (pintype "passive"))
      (node (ref "R4") (pin "1") (pinfunction "1_1") (pintype "passive"))
    )
    (net (code "34") (name "Net-(LED3-PadA)") (class "Default")
      (node (ref "LED3") (pin "A") (pinfunction "A_A") (pintype "passive"))
      (node (ref "R6") (pin "1") (pinfunction "1_1") (pintype "passive"))
    )
    (net (code "35") (name "Net-(LED4-PadA)") (class "Default")
      (node (ref "LED4") (pin "A") (pinfunction "A_A") (pintype "passive"))
      (node (ref "R7") (pin "1") (pinfunction "1_1") (pintype "passive"))
    )
    (net (code "36") (name "Net-(LED5-PadA)") (class "Default")
      (node (ref "LED5") (pin "A") (pinfunction "A_A") (pintype "passive"))
      (node (ref "R8") (pin "1") (pinfunction "1_1") (pintype "passive"))
    )
    (net (code "37") (name "Net-(Q2-PadB)") (class "Default")
      (node (ref "Q2") (pin "B") (pinfunction "B_B") (pintype "passive"))
      (node (ref "R15") (pin "2") (pinfunction "2_2") (pintype "passive"))
    )
    (net (code "38") (name "Net-(Q3-PadB)") (class "Default")
      (node (ref "Q3") (pin "B") (pinfunction "B_B") (pintype "passive"))
      (node (ref "R27") (pin "2") (pinfunction "2_2") (pintype "passive"))
    )
    (net (code "39") (name "Net-(R10-Pad1)") (class "Default")
      (node (ref "R10") (pin "1") (pinfunction "1_1") (pintype "passive"))
      (node (ref "SW4") (pin "L1") (pinfunction "L1_L1") (pintype "passive"))
    )
    (net (code "40") (name "Net-(R23-Pad1)") (class "Default")
      (node (ref "R23") (pin "1") (pinfunction "1_1") (pintype "passive"))
      (node (ref "SW6") (pin "L1") (pinfunction "L1_L1") (pintype "passive"))
    )
    (net (code "41") (name "Net-(UC1-PA4{slash}SPI1_NSS{slash}USART2_CK{slash}ADC12_IN4)") (class "Default")
      (node (ref "R4") (pin "2") (pinfunction "2_2") (pintype "passive"))
      (node (ref "UC1") (pin "14") (pinfunction "PA4/SPI1_NSS/USART2_CK/ADC12_IN4_14") (pintype "bidirectional"))
    )
    (net (code "42") (name "Net-(UC1-PA5{slash}SPI1_SCK{slash}ADC12_IN5)") (class "Default")
      (node (ref "R6") (pin "2") (pinfunction "2_2") (pintype "passive"))
      (node (ref "UC1") (pin "15") (pinfunction "PA5/SPI1_SCK/ADC12_IN5_15") (pintype "bidirectional"))
    )
    (net (code "43") (name "Net-(UC1-PA6{slash}SPI1_MISO{slash}ADC12_IN6{slash}TIM3_CH1)") (class "Default")
      (node (ref "R7") (pin "2") (pinfunction "2_2") (pintype "passive"))
      (node (ref "UC1") (pin "16") (pinfunction "PA6/SPI1_MISO/ADC12_IN6/TIM3_CH1_16") (pintype "bidirectional"))
    )
    (net (code "44") (name "Net-(UC1-PA7{slash}SPI1_MOSI{slash}ADC12_IN7{slash}TIM3_CH2)") (class "Default")
      (node (ref "R8") (pin "2") (pinfunction "2_2") (pintype "passive"))
      (node (ref "UC1") (pin "17") (pinfunction "PA7/SPI1_MOSI/ADC12_IN7/TIM3_CH2_17") (pintype "bidirectional"))
    )
    (net (code "45") (name "Net-(UC1-PB0{slash}ADC12_IN8{slash}TIM3_CH3)") (class "Default")
      (node (ref "R23") (pin "2") (pinfunction "2_2") (pintype "passive"))
      (node (ref "UC1") (pin "18") (pinfunction "PB0/ADC12_IN8/TIM3_CH3_18") (pintype "bidirectional"))
    )
    (net (code "46") (name "Net-(UC1-PB1{slash}ADC12_IN9{slash}TIM3_CH4)") (class "Default")
      (node (ref "R10") (pin "2") (pinfunction "2_2") (pintype "passive"))
      (node (ref "UC1") (pin "19") (pinfunction "PB1/ADC12_IN9/TIM3_CH4_19") (pintype "bidirectional"))
    )
    (net (code "47") (name "Net-(UC1-PB10{slash}I2C2_SCL{slash}USART3_TX)") (class "Default")
      (node (ref "R2") (pin "2") (pinfunction "2_2") (pintype "passive"))
      (node (ref "UC1") (pin "21") (pinfunction "PB10/I2C2_SCL/USART3_TX_21") (pintype "input"))
    )
    (net (code "48") (name "Net-(UC1-PD0-OSC_IN)") (class "Default")
      (node (ref "C7") (pin "2") (pinfunction "2_2") (pintype "passive"))
      (node (ref "Q1") (pin "2") (pinfunction "2_2") (pintype "passive"))
      (node (ref "UC1") (pin "5") (pinfunction "PD0-OSC_IN_5") (pintype "input"))
    )
    (net (code "49") (name "Net-(UC1-PD1-OSC_OUT)") (class "Default")
      (node (ref "C6") (pin "2") (pinfunction "2_2") (pintype "passive"))
      (node (ref "Q1") (pin "1") (pinfunction "1_1") (pintype "passive"))
      (node (ref "UC1") (pin "6") (pinfunction "PD1-OSC_OUT_6") (pintype "input"))
    )
    (net (code "50") (name "POT_1") (class "Default")
      (node (ref "R1") (pin "P$2") (pinfunction "S_P$2") (pintype "passive"))
      (node (ref "UC1") (pin "13") (pinfunction "PA3/USART2_RX/ADC12_IN3/TIM2_CH4_13") (pintype "bidirectional"))
    )
    (net (code "51") (name "POT_2") (class "Default")
      (node (ref "R5") (pin "P$2") (pinfunction "S_P$2") (pintype "passive"))
      (node (ref "UC1") (pin "12") (pinfunction "PA2/USART2_TX/ADC12_IN2/TIM2_CH3_12") (pintype "bidirectional"))
    )
    (net (code "52") (name "POT_3") (class "Default")
      (node (ref "R11") (pin "P$2") (pinfunction "S_P$2") (pintype "passive"))
      (node (ref "UC1") (pin "11") (pinfunction "PA1/USART2_RTS/ADC12_IN1/TIM2_CH2_11") (pintype "bidirectional"))
    )
    (net (code "53") (name "POT_4") (class "Default")
      (node (ref "R21") (pin "P$2") (pinfunction "S_P$2") (pintype "passive"))
      (node (ref "UC1") (pin "10") (pinfunction "PA0_WKUP/USART2_CTS/ADC12_IN0/TIM2_CH1_ETR_10") (pintype "bidirectional"))
    )
    (net (code "54") (name "RESET") (class "Default")
      (node (ref "JP2") (pin "10") (pinfunction "10_10") (pintype "passive"))
      (node (ref "R3") (pin "1") (pinfunction "1_1") (pintype "passive"))
      (node (ref "RESET") (pin "2") (pinfunction "2_2") (pintype "passive"))
      (node (ref "UC1") (pin "7") (pinfunction "NRST_7") (pintype "input"))
    )
    (net (code "55") (name "RX") (class "Default")
      (node (ref "UC1") (pin "31") (pinfunction "PA10/USART1_RX/TIM1_CH3_31") (pintype "bidirectional"))
    )
    (net (code "56") (name "SW_DUAL") (class "Default")
      (node (ref "SW2") (pin "3") (pinfunction "3_3") (pintype "passive"))
      (node (ref "SW2") (pin "4") (pinfunction "4_4") (pintype "passive"))
      (node (ref "UC1") (pin "3") (pinfunction "PC14-OSC32_IN_3") (pintype "input"))
    )
    (net (code "57") (name "SW_MODE") (class "Default")
      (node (ref "SW1") (pin "3") (pinfunction "3_3") (pintype "passive"))
      (node (ref "SW1") (pin "4") (pinfunction "4_4") (pintype "passive"))
      (node (ref "UC1") (pin "2") (pinfunction "PC13-TAMPER-RTC_2") (pintype "input"))
    )
    (net (code "58") (name "SW_TRIG_1") (class "Default")
      (node (ref "SW6") (pin "P$1") (pinfunction "P$1_P$1") (pintype "bidirectional"))
      (node (ref "SW6") (pin "P$2") (pinfunction "P$2_P$2") (pintype "bidirectional"))
      (node (ref "UC1") (pin "40") (pinfunction "PB4/NJTRST_40") (pintype "bidirectional"))
    )
    (net (code "59") (name "SW_TRIG_2") (class "Default")
      (node (ref "SW4") (pin "P$1") (pinfunction "P$1_P$1") (pintype "bidirectional"))
      (node (ref "SW4") (pin "P$2") (pinfunction "P$2_P$2") (pintype "bidirectional"))
      (node (ref "UC1") (pin "29") (pinfunction "PA8/USART1_CK/TIM1_CH1/MCO_29") (pintype "bidirectional"))
    )
    (net (code "60") (name "TRIG_1") (class "Default")
      (node (ref "Q3") (pin "C") (pinfunction "C_C") (pintype "passive"))
      (node (ref "R28") (pin "1") (pinfunction "1_1") (pintype "passive"))
      (node (ref "UC1") (pin "33") (pinfunction "PA12/USART1_RTS/CAN_TX/TIM1_ETR/USBDP_33") (pintype "bidirectional"))
    )
    (net (code "61") (name "TRIG_2") (class "Default")
      (node (ref "Q2") (pin "C") (pinfunction "C_C") (pintype "passive"))
      (node (ref "R16") (pin "1") (pinfunction "1_1") (pintype "passive"))
      (node (ref "UC1") (pin "22") (pinfunction "PB11/I2C2_SDA/USART3_RX_22") (pintype "input"))
    )
    (net (code "62") (name "TX") (class "Default")
      (node (ref "UC1") (pin "30") (pinfunction "PA9/USART1_TX/TIM1_CH2_30") (pintype "input"))
    )
    (net (code "63") (name "VCC") (class "Default")
      (node (ref "C16") (pin "1") (pinfunction "1_1") (pintype "passive"))
      (node (ref "C2") (pin "+") (pinfunction "+_+") (pintype "passive"))
      (node (ref "C21") (pin "1") (pinfunction "1_1") (pintype "passive"))
      (node (ref "D1") (pin "C") (pinfunction "C_C") (pintype "passive"))
      (node (ref "IC1") (pin "3") (pinfunction "VIN_3") (pintype "input"))
      (node (ref "IC4") (pin "8") (pinfunction "V+_8") (pintype "power_in"))
      (node (ref "IC5") (pin "8") (pinfunction "V+_8") (pintype "power_in"))
    )
    (net (code "64") (name "VEE") (class "Default")
      (node (ref "C1") (pin "-") (pinfunction "-_-") (pintype "passive"))
      (node (ref "C18") (pin "2") (pinfunction "2_2") (pintype "passive"))
      (node (ref "C24") (pin "2") (pinfunction "2_2") (pintype "passive"))
      (node (ref "D2") (pin "A") (pinfunction "A_A") (pintype "passive"))
      (node (ref "IC4") (pin "4") (pinfunction "V-_4") (pintype "power_in"))
      (node (ref "IC5") (pin "4") (pinfunction "V-_4") (pintype "power_in"))
      (node (ref "R25") (pin "1") (pinfunction "1_1") (pintype "passive"))
    )
    (net (code "65") (name "unconnected-(J3-2-PadP2)") (class "Default")
      (node (ref "J3") (pin "P2") (pinfunction "2_P2") (pintype "passive"))
    )
    (net (code "66") (name "unconnected-(J4-2-PadP2)") (class "Default")
      (node (ref "J4") (pin "P2") (pinfunction "2_P2") (pintype "passive"))
    )
    (net (code "67") (name "unconnected-(JP2-Pad7)") (class "Default")
      (node (ref "JP2") (pin "7") (pinfunction "7_7") (pintype "passive"))
    )
    (net (code "68") (name "unconnected-(UC1-PA11{slash}USART1_CTS{slash}CAN_RX{slash}TIM1_CH4{slash}USBDM-Pad32)") (class "Default")
      (node (ref "UC1") (pin "32") (pinfunction "PA11/USART1_CTS/CAN_RX/TIM1_CH4/USBDM_32") (pintype "bidirectional"))
    )
    (net (code "69") (name "unconnected-(UC1-PB5{slash}I2C1_SMBA-Pad41)") (class "Default")
      (node (ref "UC1") (pin "41") (pinfunction "PB5/I2C1_SMBA_41") (pintype "input"))
    )
    (net (code "70") (name "unconnected-(UC1-PB6{slash}I2C1_SCL{slash}TIM4_CH1-Pad42)") (class "Default")
      (node (ref "UC1") (pin "42") (pinfunction "PB6/I2C1_SCL/TIM4_CH1_42") (pintype "input"))
    )
    (net (code "71") (name "unconnected-(UC1-PB7{slash}I2C1_SDA{slash}TIM4_CH2-Pad43)") (class "Default")
      (node (ref "UC1") (pin "43") (pinfunction "PB7/I2C1_SDA/TIM4_CH2_43") (pintype "bidirectional"))
    )
    (net (code "72") (name "unconnected-(UC1-PB8{slash}TIM4_CH3-Pad45)") (class "Default")
      (node (ref "UC1") (pin "45") (pinfunction "PB8/TIM4_CH3_45") (pintype "bidirectional"))
    )
    (net (code "73") (name "unconnected-(UC1-PB14{slash}SPI2_MISO{slash}USART3_RTS{slash}TIM1_CH2N-Pad27)") (class "Default")
      (node (ref "UC1") (pin "27") (pinfunction "PB14/SPI2_MISO/USART3_RTS/TIM1_CH2N_27") (pintype "input"))
    )
    (net (code "74") (name "unconnected-(UC1-PC15-OSC32_OUT-Pad4)") (class "Default")
      (node (ref "UC1") (pin "4") (pinfunction "PC15-OSC32_OUT_4") (pintype "input"))
    )
  )
)
